# GSM_Velvet_Controller.net
KiCad netlist of a schematic drawn in Altium Designer
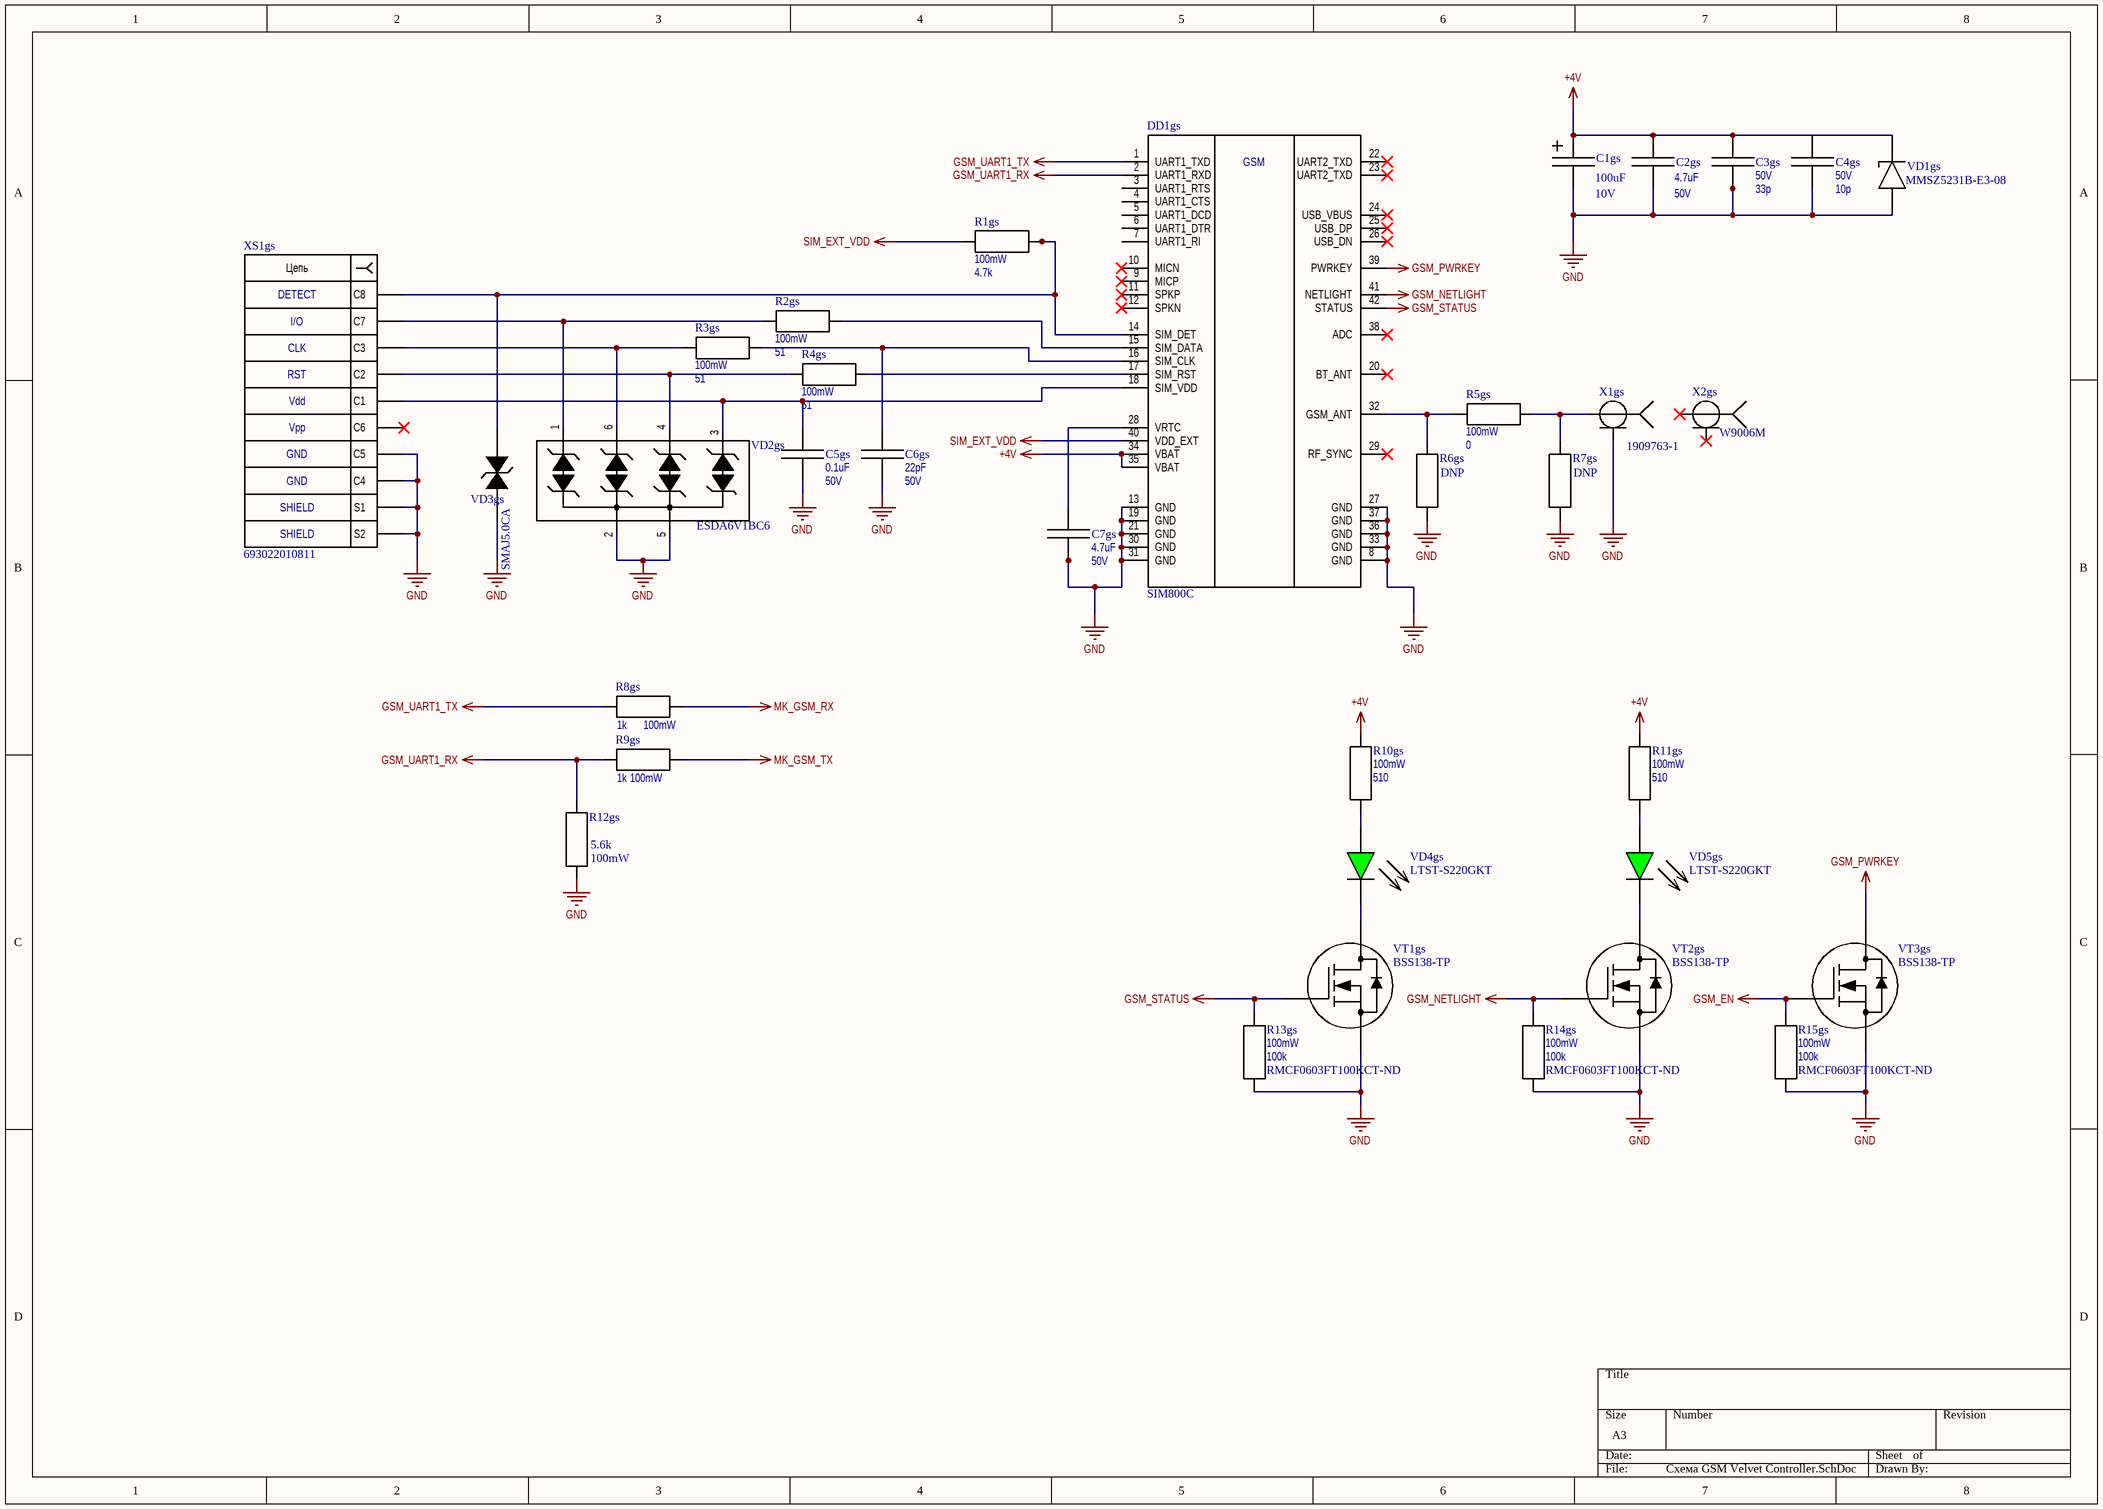
[diagram p0: Схема GSM Velvet Controller.SchDoc]

(export (version "E")
  (design (tool "Eeschema 10.0.6"))
  (components
    (comp (ref "C1gs")
      (value "TPSD107M010R0050")
      (footprint "CAP 2917 (D)")
      (description "CAP SMD TANT 100UF 20% 10V 2917")
      (fields
        (field (name "CAPACITANCE") "100uF")
        (field (name "TOLERANCE") "20%")
        (field (name "RATED VOLTAGE") "10V")
      )
      (libsource (lib "Passive components") (part "TPSD107M010R0050"))
    )
    (comp (ref "C2gs")
      (value "CL21A475KBQNNNE")
      (footprint "CAP 0805 IPC MAX")
      (description "CAP SMD CER 4.7UF 50V X5R 0805")
      (fields
        (field (name "TOLERANCE") "10%")
        (field (name "CAPACITANCE") "4.7uF")
        (field (name "RATED VOLTAGE") "50V")
      )
      (libsource (lib "Passive components") (part "CL21A475KBQNNNE"))
    )
    (comp (ref "C3gs")
      (value "C0603C330J5GAC7867")
      (footprint "CAP 0603 IPC MAX")
      (description "CAP SMD CER 33PF 50V C0G/NP0 0603")
      (fields
        (field (name "TOLERANCE") "5%")
        (field (name "RATED VOLTAGE") "50V")
        (field (name "CAPACITANCE") "33p")
      )
      (libsource (lib "Passive components") (part "C0603C330J5GAC7867"))
    )
    (comp (ref "C4gs")
      (value "CC0603JRNPO9BN100")
      (footprint "CAP 0603 IPC MAX")
      (description "CAP SMD CER 10PF 50V C0G/NP0 0603")
      (fields
        (field (name "TOLERANCE") "5%")
        (field (name "RATED VOLTAGE") "50V")
        (field (name "CAPACITANCE") "10p")
      )
      (libsource (lib "Passive components") (part "CC0603JRNPO9BN100"))
    )
    (comp (ref "C5gs")
      (value "GCM188R71H104KA57D")
      (footprint "CAP 0603 IPC MAX")
      (description "CAP SMD CER 0.1UF 50V X7R 0603")
      (fields
        (field (name "TOLERANCE") "10%")
        (field (name "CAPACITANCE") "0.1uF")
        (field (name "RATED VOLTAGE") "50V")
      )
      (libsource (lib "Passive components") (part "GCM188R71H104KA57D"))
    )
    (comp (ref "C6gs")
      (value "CC0603JRNPO9BN220")
      (footprint "CAP 0603 IPC MAX")
      (description "CAP SMD CER 22PF 50V NP0  0603")
      (fields
        (field (name "TOLERANCE") "5%")
        (field (name "CAPACITANCE") "22pF")
        (field (name "RATED VOLTAGE") "50V")
      )
      (libsource (lib "Passive components") (part "CC0603JRNPO9BN220"))
    )
    (comp (ref "C7gs")
      (value "CL21A475KBQNNNE")
      (footprint "CAP 0805 IPC MAX")
      (description "CAP SMD CER 4.7UF 50V X5R 0805")
      (fields
        (field (name "TOLERANCE") "10%")
        (field (name "CAPACITANCE") "4.7uF")
        (field (name "RATED VOLTAGE") "50V")
      )
      (libsource (lib "Passive components") (part "CL21A475KBQNNNE"))
    )
    (comp (ref "DD1gs")
      (value "SIM800C")
      (footprint "SIM-800C")
      (description "GSM/GPRS Module")
      (libsource (lib "Digital") (part "SIM800C"))
    )
    (comp (ref "R1gs")
      (value "RMCF0603FT4K70")
      (footprint "RES 0603 IPC MAX")
      (description "RES SMD 4.7k OHM 1% 1/10W 0603")
      (fields
        (field (name "TOLERANCE") "1%")
        (field (name "RATED POWER") "100mW")
        (field (name "RESISTANCE") "4.7k")
      )
      (libsource (lib "Passive components") (part "RMCF0603FT4K70"))
    )
    (comp (ref "R2gs")
      (value "RMCF0603FT51R0")
      (footprint "RES 0603 IPC MAX")
      (description "RES SMD 51 OHM 1% 1/10W 0603")
      (fields
        (field (name "TOLERANCE") "1%")
        (field (name "RATED POWER") "100mW")
        (field (name "RESISTANCE") "51")
      )
      (libsource (lib "Passive components") (part "RMCF0603FT51R0"))
    )
    (comp (ref "R3gs")
      (value "RMCF0603FT51R0")
      (footprint "RES 0603 IPC MAX")
      (description "RES SMD 51 OHM 1% 1/10W 0603")
      (fields
        (field (name "TOLERANCE") "1%")
        (field (name "RATED POWER") "100mW")
        (field (name "RESISTANCE") "51")
      )
      (libsource (lib "Passive components") (part "RMCF0603FT51R0"))
    )
    (comp (ref "R4gs")
      (value "RMCF0603FT51R0")
      (footprint "RES 0603 IPC MAX")
      (description "RES SMD 51 OHM 1% 1/10W 0603")
      (fields
        (field (name "TOLERANCE") "1%")
        (field (name "RATED POWER") "100mW")
        (field (name "RESISTANCE") "51")
      )
      (libsource (lib "Passive components") (part "RMCF0603FT51R0"))
    )
    (comp (ref "R5gs")
      (value "RMCF0603ZT0R00")
      (footprint "RES 0603 IPC MAX")
      (description "RES SMD 0 OHM 1% 1/10W 0603")
      (fields
        (field (name "TOLERANCE") "1%")
        (field (name "RATED POWER") "100mW")
        (field (name "RESISTANCE") "0")
      )
      (libsource (lib "Passive components") (part "RMCF0603ZT0R00"))
    )
    (comp (ref "R6gs")
      (value "DNP")
      (footprint "RES 0603 IPC MAX")
      (description "RES SMD/TH ?R (&K) OHM ?% ?W (PACKAGE)")
      (libsource (lib "Passive components") (part "RES GOST"))
    )
    (comp (ref "R7gs")
      (value "DNP")
      (footprint "RES 0603 IPC MAX")
      (description "RES SMD/TH ?R (&K) OHM ?% ?W (PACKAGE)")
      (libsource (lib "Passive components") (part "RES GOST"))
    )
    (comp (ref "R8gs")
      (value "RMCF0603FT1K00")
      (footprint "RES 0603 IPC MAX")
      (description "RES SMD 1K OHM 1% 1/10W 0603")
      (fields
        (field (name "RESISTANCE") "1k")
        (field (name "TOLERANCE") "1%")
        (field (name "RATED POWER") "100mW")
      )
      (libsource (lib "Passive components") (part "RMCF0603FT1K00"))
    )
    (comp (ref "R9gs")
      (value "RMCF0603FT1K00")
      (footprint "RES 0603 IPC MAX")
      (description "RES SMD 1K OHM 1% 1/10W 0603")
      (fields
        (field (name "RESISTANCE") "1k")
        (field (name "TOLERANCE") "1%")
        (field (name "RATED POWER") "100mW")
      )
      (libsource (lib "Passive components") (part "RMCF0603FT1K00"))
    )
    (comp (ref "R10gs")
      (value "RMCF0603JT510R")
      (footprint "RES 0603 IPC MAX")
      (description "RES SMD 510 OHM 5% 1/10W 0603")
      (fields
        (field (name "TOLERANCE") "5%")
        (field (name "POWER RATED") "100mW")
        (field (name "RESISTANCE") "510")
      )
      (libsource (lib "Passive components") (part "RMCF0603JT510R"))
    )
    (comp (ref "R11gs")
      (value "RMCF0603JT510R")
      (footprint "RES 0603 IPC MAX")
      (description "RES SMD 510 OHM 5% 1/10W 0603")
      (fields
        (field (name "TOLERANCE") "5%")
        (field (name "POWER RATED") "100mW")
        (field (name "RESISTANCE") "510")
      )
      (libsource (lib "Passive components") (part "RMCF0603JT510R"))
    )
    (comp (ref "R12gs")
      (value "RMCF0603FT5K60")
      (footprint "RES 0603 IPC MAX")
      (description "RES SMD 5.6K OHM 1% 1/10W 0603")
      (fields
        (field (name "RESISTANCE") "5.6k")
        (field (name "TOLERANCE") "1%")
        (field (name "RATED POWER") "100mW")
      )
      (libsource (lib "Passive components") (part "RMCF0603FT5K60"))
    )
    (comp (ref "R13gs")
      (value "RMCF0603FT100K")
      (footprint "RES 0603 IPC MAX")
      (description "RES SMD 100K OHM 5% 1/10W 0603")
      (fields
        (field (name "TOLERANCE") "5%")
        (field (name "POWER RATED") "100mW")
        (field (name "RESISTANCE") "100k")
        (field (name "SUPPLIER PART NUMBER 1") "RMCF0603FT100KCT-ND")
      )
      (libsource (lib "Passive components") (part "RMCF0603FT100K"))
    )
    (comp (ref "R14gs")
      (value "RMCF0603FT100K")
      (footprint "RES 0603 IPC MAX")
      (description "RES SMD 100K OHM 5% 1/10W 0603")
      (fields
        (field (name "TOLERANCE") "5%")
        (field (name "POWER RATED") "100mW")
        (field (name "RESISTANCE") "100k")
        (field (name "SUPPLIER PART NUMBER 1") "RMCF0603FT100KCT-ND")
      )
      (libsource (lib "Passive components") (part "RMCF0603FT100K"))
    )
    (comp (ref "R15gs")
      (value "RMCF0603FT100K")
      (footprint "RES 0603 IPC MAX")
      (description "RES SMD 100K OHM 5% 1/10W 0603")
      (fields
        (field (name "TOLERANCE") "5%")
        (field (name "POWER RATED") "100mW")
        (field (name "RESISTANCE") "100k")
        (field (name "SUPPLIER PART NUMBER 1") "RMCF0603FT100KCT-ND")
      )
      (libsource (lib "Passive components") (part "RMCF0603FT100K"))
    )
    (comp (ref "VD1gs")
      (value "MMSZ5231B-E3-08")
      (footprint "SOD-123 (Marked)")
      (description "DIODE ZENER 5.1V 500MW SOD123")
      (fields (field (name "TOLERANCE") "5%"))
      (libsource (lib "Diodes") (part "MMSZ5231B-E3-08"))
    )
    (comp (ref "VD2gs")
      (value "ESDA6V1BC6")
      (footprint "SOT-23-6")
      (description "TVS DIODE 5VWM SOT23-6")
      (libsource (lib "Diodes") (part "ESDA6V1BC6"))
    )
    (comp (ref "VD3gs")
      (value "SMAJ5.0CA")
      (footprint "DO-214AC Bidirectional")
      (description "TVS DIODE 5VWM 9.2VC DO214AC")
      (libsource (lib "Diodes") (part "SMAJ5.0CA"))
    )
    (comp (ref "VD4gs")
      (value "LTST-S220GKT")
      (footprint "0805 DIODE")
      (description "LED GREEN CLEAR SMD R/A")
      (libsource (lib "Diodes") (part "LTST-S220GKT"))
    )
    (comp (ref "VD5gs")
      (value "LTST-S220GKT")
      (footprint "0805 DIODE")
      (description "LED GREEN CLEAR SMD R/A")
      (libsource (lib "Diodes") (part "LTST-S220GKT"))
    )
    (comp (ref "VT1gs")
      (value "BSS138-TP")
      (footprint "SOT-23-3")
      (description "MOSFET N-CH 50V 220MA SOT23")
      (libsource (lib "MOSFET") (part "BSS138-TP"))
    )
    (comp (ref "VT2gs")
      (value "BSS138-TP")
      (footprint "SOT-23-3")
      (description "MOSFET N-CH 50V 220MA SOT23")
      (libsource (lib "MOSFET") (part "BSS138-TP"))
    )
    (comp (ref "VT3gs")
      (value "BSS138-TP")
      (footprint "SOT-23-3")
      (description "MOSFET N-CH 50V 220MA SOT23")
      (libsource (lib "MOSFET") (part "BSS138-TP"))
    )
    (comp (ref "X1gs")
      (value "1909763-1")
      (footprint "1909763-1")
      (description "CONN UMCC JACK STR 50OHM SMD")
      (libsource (lib "Connectors") (part "1909763-1"))
    )
    (comp (ref "X2gs")
      (value "W9006M")
      (description "CABLE ASSY 6\" SMA FM TO I-PEX")
      (libsource (lib "Connectors") (part "W9006M"))
    )
    (comp (ref "XS1gs")
      (value "693022010811")
      (footprint "693022010811")
      (description "CONN SMART CARD")
      (libsource (lib "Connectors") (part "693022010811"))
    )
  )
  (nets
    (net (code "1") (name "+4V") (class "Default")
      (node (ref "C1gs") (pin "1") (pinfunction "1_1") (pintype "passive"))
      (node (ref "C2gs") (pin "1") (pinfunction "1_1") (pintype "passive"))
      (node (ref "C3gs") (pin "1") (pinfunction "1_1") (pintype "passive"))
      (node (ref "C4gs") (pin "1") (pinfunction "1_1") (pintype "passive"))
      (node (ref "DD1gs") (pin "34") (pinfunction "VBAT_34") (pintype "passive"))
      (node (ref "DD1gs") (pin "35") (pinfunction "VBAT_35") (pintype "passive"))
      (node (ref "R10gs") (pin "2") (pinfunction "2_2") (pintype "passive"))
      (node (ref "R11gs") (pin "2") (pinfunction "2_2") (pintype "passive"))
      (node (ref "VD1gs") (pin "1") (pinfunction "1_1") (pintype "passive"))
    )
    (net (code "2") (name "GND") (class "Default")
      (node (ref "C1gs") (pin "2") (pinfunction "2_2") (pintype "passive"))
      (node (ref "C2gs") (pin "2") (pinfunction "2_2") (pintype "passive"))
      (node (ref "C3gs") (pin "2") (pinfunction "2_2") (pintype "passive"))
      (node (ref "C4gs") (pin "2") (pinfunction "2_2") (pintype "passive"))
      (node (ref "C5gs") (pin "2") (pinfunction "2_2") (pintype "passive"))
      (node (ref "C6gs") (pin "2") (pinfunction "2_2") (pintype "passive"))
      (node (ref "C7gs") (pin "2") (pinfunction "2_2") (pintype "passive"))
      (node (ref "DD1gs") (pin "13") (pinfunction "GND_13") (pintype "passive"))
      (node (ref "DD1gs") (pin "19") (pinfunction "GND_19") (pintype "passive"))
      (node (ref "DD1gs") (pin "21") (pinfunction "GND_21") (pintype "passive"))
      (node (ref "DD1gs") (pin "27") (pinfunction "GND_27") (pintype "passive"))
      (node (ref "DD1gs") (pin "30") (pinfunction "GND_30") (pintype "passive"))
      (node (ref "DD1gs") (pin "31") (pinfunction "GND_31") (pintype "passive"))
      (node (ref "DD1gs") (pin "33") (pinfunction "GND_33") (pintype "passive"))
      (node (ref "DD1gs") (pin "36") (pinfunction "GND_36") (pintype "passive"))
      (node (ref "DD1gs") (pin "37") (pinfunction "GND_37") (pintype "passive"))
      (node (ref "DD1gs") (pin "8") (pinfunction "GND_8") (pintype "passive"))
      (node (ref "R12gs") (pin "1") (pinfunction "1_1") (pintype "passive"))
      (node (ref "R13gs") (pin "1") (pinfunction "1_1") (pintype "passive"))
      (node (ref "R14gs") (pin "1") (pinfunction "1_1") (pintype "passive"))
      (node (ref "R15gs") (pin "1") (pinfunction "1_1") (pintype "passive"))
      (node (ref "R6gs") (pin "1") (pinfunction "1_1") (pintype "passive"))
      (node (ref "R7gs") (pin "1") (pinfunction "1_1") (pintype "passive"))
      (node (ref "VD1gs") (pin "2") (pinfunction "2_2") (pintype "passive"))
      (node (ref "VD2gs") (pin "2") (pinfunction "2_2") (pintype "passive"))
      (node (ref "VD2gs") (pin "5") (pinfunction "5_5") (pintype "passive"))
      (node (ref "VD3gs") (pin "1") (pinfunction "1_1") (pintype "passive"))
      (node (ref "VT1gs") (pin "2") (pinfunction "S_2") (pintype "passive"))
      (node (ref "VT2gs") (pin "2") (pinfunction "S_2") (pintype "passive"))
      (node (ref "VT3gs") (pin "2") (pinfunction "S_2") (pintype "passive"))
      (node (ref "X1gs") (pin "2") (pinfunction "2_2") (pintype "passive"))
      (node (ref "XS1gs") (pin "C4") (pinfunction "C4_C4") (pintype "passive"))
      (node (ref "XS1gs") (pin "C5") (pinfunction "C5_C5") (pintype "passive"))
      (node (ref "XS1gs") (pin "S1") (pinfunction "S1_S1") (pintype "passive"))
      (node (ref "XS1gs") (pin "S2") (pinfunction "S2_S2") (pintype "passive"))
    )
    (net (code "3") (name "GSM_EN") (class "Default")
      (node (ref "R15gs") (pin "2") (pinfunction "2_2") (pintype "passive"))
      (node (ref "VT3gs") (pin "1") (pinfunction "G_1") (pintype "passive"))
    )
    (net (code "4") (name "GSM_NETLIGHT") (class "Default")
      (node (ref "DD1gs") (pin "41") (pinfunction "NETLIGHT_41") (pintype "passive"))
      (node (ref "R14gs") (pin "2") (pinfunction "2_2") (pintype "passive"))
      (node (ref "VT2gs") (pin "1") (pinfunction "G_1") (pintype "passive"))
    )
    (net (code "5") (name "GSM_PWRKEY") (class "Default")
      (node (ref "DD1gs") (pin "39") (pinfunction "PWRKEY_39") (pintype "passive"))
      (node (ref "VT3gs") (pin "3") (pinfunction "D_3") (pintype "passive"))
    )
    (net (code "6") (name "GSM_STATUS") (class "Default")
      (node (ref "DD1gs") (pin "42") (pinfunction "STATUS_42") (pintype "passive"))
      (node (ref "R13gs") (pin "2") (pinfunction "2_2") (pintype "passive"))
      (node (ref "VT1gs") (pin "1") (pinfunction "G_1") (pintype "passive"))
    )
    (net (code "7") (name "GSM_UART1_RX") (class "Default")
      (node (ref "DD1gs") (pin "2") (pinfunction "UART1_RXD_2") (pintype "passive"))
      (node (ref "R12gs") (pin "2") (pinfunction "2_2") (pintype "passive"))
      (node (ref "R9gs") (pin "1") (pinfunction "1_1") (pintype "passive"))
    )
    (net (code "8") (name "GSM_UART1_TX") (class "Default")
      (node (ref "DD1gs") (pin "1") (pinfunction "UART1_TXD_1") (pintype "passive"))
      (node (ref "R8gs") (pin "1") (pinfunction "1_1") (pintype "passive"))
    )
    (net (code "9") (name "MK_GSM_RX") (class "Default")
      (node (ref "R8gs") (pin "2") (pinfunction "2_2") (pintype "passive"))
    )
    (net (code "10") (name "MK_GSM_TX") (class "Default")
      (node (ref "R9gs") (pin "2") (pinfunction "2_2") (pintype "passive"))
    )
    (net (code "11") (name "Net-(DD1gs-GSM_ANT)") (class "Default")
      (node (ref "DD1gs") (pin "32") (pinfunction "GSM_ANT_32") (pintype "passive"))
      (node (ref "R5gs") (pin "1") (pinfunction "1_1") (pintype "passive"))
      (node (ref "R6gs") (pin "2") (pinfunction "2_2") (pintype "passive"))
    )
    (net (code "12") (name "Net-(DD1gs-SIM_CLK)") (class "Default")
      (node (ref "C6gs") (pin "1") (pinfunction "1_1") (pintype "passive"))
      (node (ref "DD1gs") (pin "16") (pinfunction "SIM_CLK_16") (pintype "passive"))
      (node (ref "R3gs") (pin "2") (pinfunction "2_2") (pintype "passive"))
    )
    (net (code "13") (name "Net-(DD1gs-SIM_DATA)") (class "Default")
      (node (ref "DD1gs") (pin "15") (pinfunction "SIM_DATA_15") (pintype "passive"))
      (node (ref "R2gs") (pin "2") (pinfunction "2_2") (pintype "passive"))
    )
    (net (code "14") (name "Net-(DD1gs-SIM_DET)") (class "Default")
      (node (ref "DD1gs") (pin "14") (pinfunction "SIM_DET_14") (pintype "passive"))
      (node (ref "R1gs") (pin "2") (pinfunction "2_2") (pintype "passive"))
      (node (ref "VD3gs") (pin "2") (pinfunction "2_2") (pintype "passive"))
      (node (ref "XS1gs") (pin "C8") (pinfunction "C8_C8") (pintype "passive"))
    )
    (net (code "15") (name "Net-(DD1gs-SIM_RST)") (class "Default")
      (node (ref "DD1gs") (pin "17") (pinfunction "SIM_RST_17") (pintype "passive"))
      (node (ref "R4gs") (pin "2") (pinfunction "2_2") (pintype "passive"))
    )
    (net (code "16") (name "Net-(DD1gs-SIM_VDD)") (class "Default")
      (node (ref "C5gs") (pin "1") (pinfunction "1_1") (pintype "passive"))
      (node (ref "DD1gs") (pin "18") (pinfunction "SIM_VDD_18") (pintype "passive"))
      (node (ref "VD2gs") (pin "3") (pinfunction "3_3") (pintype "passive"))
      (node (ref "XS1gs") (pin "C1") (pinfunction "C1_C1") (pintype "passive"))
    )
    (net (code "17") (name "Net-(DD1gs-VRTC)") (class "Default")
      (node (ref "C7gs") (pin "1") (pinfunction "1_1") (pintype "passive"))
      (node (ref "DD1gs") (pin "28") (pinfunction "VRTC_28") (pintype "passive"))
    )
    (net (code "18") (name "Net-(R2gs-Pad1)") (class "Default")
      (node (ref "R2gs") (pin "1") (pinfunction "1_1") (pintype "passive"))
      (node (ref "VD2gs") (pin "1") (pinfunction "1_1") (pintype "passive"))
      (node (ref "XS1gs") (pin "C7") (pinfunction "C7_C7") (pintype "passive"))
    )
    (net (code "19") (name "Net-(R3gs-Pad1)") (class "Default")
      (node (ref "R3gs") (pin "1") (pinfunction "1_1") (pintype "passive"))
      (node (ref "VD2gs") (pin "6") (pinfunction "6_6") (pintype "passive"))
      (node (ref "XS1gs") (pin "C3") (pinfunction "C3_C3") (pintype "passive"))
    )
    (net (code "20") (name "Net-(R4gs-Pad1)") (class "Default")
      (node (ref "R4gs") (pin "1") (pinfunction "1_1") (pintype "passive"))
      (node (ref "VD2gs") (pin "4") (pinfunction "4_4") (pintype "passive"))
      (node (ref "XS1gs") (pin "C2") (pinfunction "C2_C2") (pintype "passive"))
    )
    (net (code "21") (name "Net-(R5gs-Pad2)") (class "Default")
      (node (ref "R5gs") (pin "2") (pinfunction "2_2") (pintype "passive"))
      (node (ref "R7gs") (pin "2") (pinfunction "2_2") (pintype "passive"))
      (node (ref "X1gs") (pin "1") (pinfunction "1_1") (pintype "passive"))
    )
    (net (code "22") (name "Net-(R10gs-Pad1)") (class "Default")
      (node (ref "R10gs") (pin "1") (pinfunction "1_1") (pintype "passive"))
      (node (ref "VD4gs") (pin "1") (pinfunction "1_1") (pintype "passive"))
    )
    (net (code "23") (name "Net-(R11gs-Pad1)") (class "Default")
      (node (ref "R11gs") (pin "1") (pinfunction "1_1") (pintype "passive"))
      (node (ref "VD5gs") (pin "1") (pinfunction "1_1") (pintype "passive"))
    )
    (net (code "24") (name "Net-(VT1gs-D)") (class "Default")
      (node (ref "VD4gs") (pin "2") (pinfunction "2_2") (pintype "passive"))
      (node (ref "VT1gs") (pin "3") (pinfunction "D_3") (pintype "passive"))
    )
    (net (code "25") (name "Net-(VT2gs-D)") (class "Default")
      (node (ref "VD5gs") (pin "2") (pinfunction "2_2") (pintype "passive"))
      (node (ref "VT2gs") (pin "3") (pinfunction "D_3") (pintype "passive"))
    )
    (net (code "26") (name "SIM_EXT_VDD") (class "Default")
      (node (ref "DD1gs") (pin "40") (pinfunction "VDD_EXT_40") (pintype "passive"))
      (node (ref "R1gs") (pin "1") (pinfunction "1_1") (pintype "passive"))
    )
    (net (code "27") (name "unconnected-(DD1gs-ADC-Pad38)") (class "Default")
      (node (ref "DD1gs") (pin "38") (pinfunction "ADC_38") (pintype "passive+no_connect"))
    )
    (net (code "28") (name "unconnected-(DD1gs-BT_ANT-Pad20)") (class "Default")
      (node (ref "DD1gs") (pin "20") (pinfunction "BT_ANT_20") (pintype "passive+no_connect"))
    )
    (net (code "29") (name "unconnected-(DD1gs-MICN-Pad10)") (class "Default")
      (node (ref "DD1gs") (pin "10") (pinfunction "MICN_10") (pintype "passive+no_connect"))
    )
    (net (code "30") (name "unconnected-(DD1gs-MICP-Pad9)") (class "Default")
      (node (ref "DD1gs") (pin "9") (pinfunction "MICP_9") (pintype "passive+no_connect"))
    )
    (net (code "31") (name "unconnected-(DD1gs-RF_SYNC-Pad29)") (class "Default")
      (node (ref "DD1gs") (pin "29") (pinfunction "RF_SYNC_29") (pintype "passive+no_connect"))
    )
    (net (code "32") (name "unconnected-(DD1gs-SPKN-Pad12)") (class "Default")
      (node (ref "DD1gs") (pin "12") (pinfunction "SPKN_12") (pintype "passive+no_connect"))
    )
    (net (code "33") (name "unconnected-(DD1gs-SPKP-Pad11)") (class "Default")
      (node (ref "DD1gs") (pin "11") (pinfunction "SPKP_11") (pintype "passive+no_connect"))
    )
    (net (code "34") (name "unconnected-(DD1gs-UART1_CTS-Pad4)") (class "Default")
      (node (ref "DD1gs") (pin "4") (pinfunction "UART1_CTS_4") (pintype "passive"))
    )
    (net (code "35") (name "unconnected-(DD1gs-UART1_DCD-Pad5)") (class "Default")
      (node (ref "DD1gs") (pin "5") (pinfunction "UART1_DCD_5") (pintype "passive"))
    )
    (net (code "36") (name "unconnected-(DD1gs-UART1_DTR-Pad6)") (class "Default")
      (node (ref "DD1gs") (pin "6") (pinfunction "UART1_DTR_6") (pintype "passive"))
    )
    (net (code "37") (name "unconnected-(DD1gs-UART1_RI-Pad7)") (class "Default")
      (node (ref "DD1gs") (pin "7") (pinfunction "UART1_RI_7") (pintype "passive"))
    )
    (net (code "38") (name "unconnected-(DD1gs-UART1_RTS-Pad3)") (class "Default")
      (node (ref "DD1gs") (pin "3") (pinfunction "UART1_RTS_3") (pintype "passive"))
    )
    (net (code "39") (name "unconnected-(DD1gs-UART2_TXD-Pad22)") (class "Default")
      (node (ref "DD1gs") (pin "22") (pinfunction "UART2_TXD_22") (pintype "passive+no_connect"))
    )
    (net (code "40") (name "unconnected-(DD1gs-UART2_TXD-Pad23)") (class "Default")
      (node (ref "DD1gs") (pin "23") (pinfunction "UART2_TXD_23") (pintype "passive+no_connect"))
    )
    (net (code "41") (name "unconnected-(DD1gs-USB_DN-Pad26)") (class "Default")
      (node (ref "DD1gs") (pin "26") (pinfunction "USB_DN_26") (pintype "passive+no_connect"))
    )
    (net (code "42") (name "unconnected-(DD1gs-USB_DP-Pad25)") (class "Default")
      (node (ref "DD1gs") (pin "25") (pinfunction "USB_DP_25") (pintype "passive+no_connect"))
    )
    (net (code "43") (name "unconnected-(DD1gs-USB_VBUS-Pad24)") (class "Default")
      (node (ref "DD1gs") (pin "24") (pinfunction "USB_VBUS_24") (pintype "passive+no_connect"))
    )
    (net (code "44") (name "unconnected-(X2gs-Pad1)") (class "Default")
      (node (ref "X2gs") (pin "1") (pinfunction "1_1") (pintype "passive+no_connect"))
    )
    (net (code "45") (name "unconnected-(X2gs-Pad2)") (class "Default")
      (node (ref "X2gs") (pin "2") (pinfunction "2_2") (pintype "passive+no_connect"))
    )
    (net (code "46") (name "unconnected-(XS1gs-PadC6)") (class "Default")
      (node (ref "XS1gs") (pin "C6") (pinfunction "C6_C6") (pintype "passive+no_connect"))
    )
  )
)
